# MugTempSensor2_0.net
KiCad netlist of a schematic drawn in EAGLE
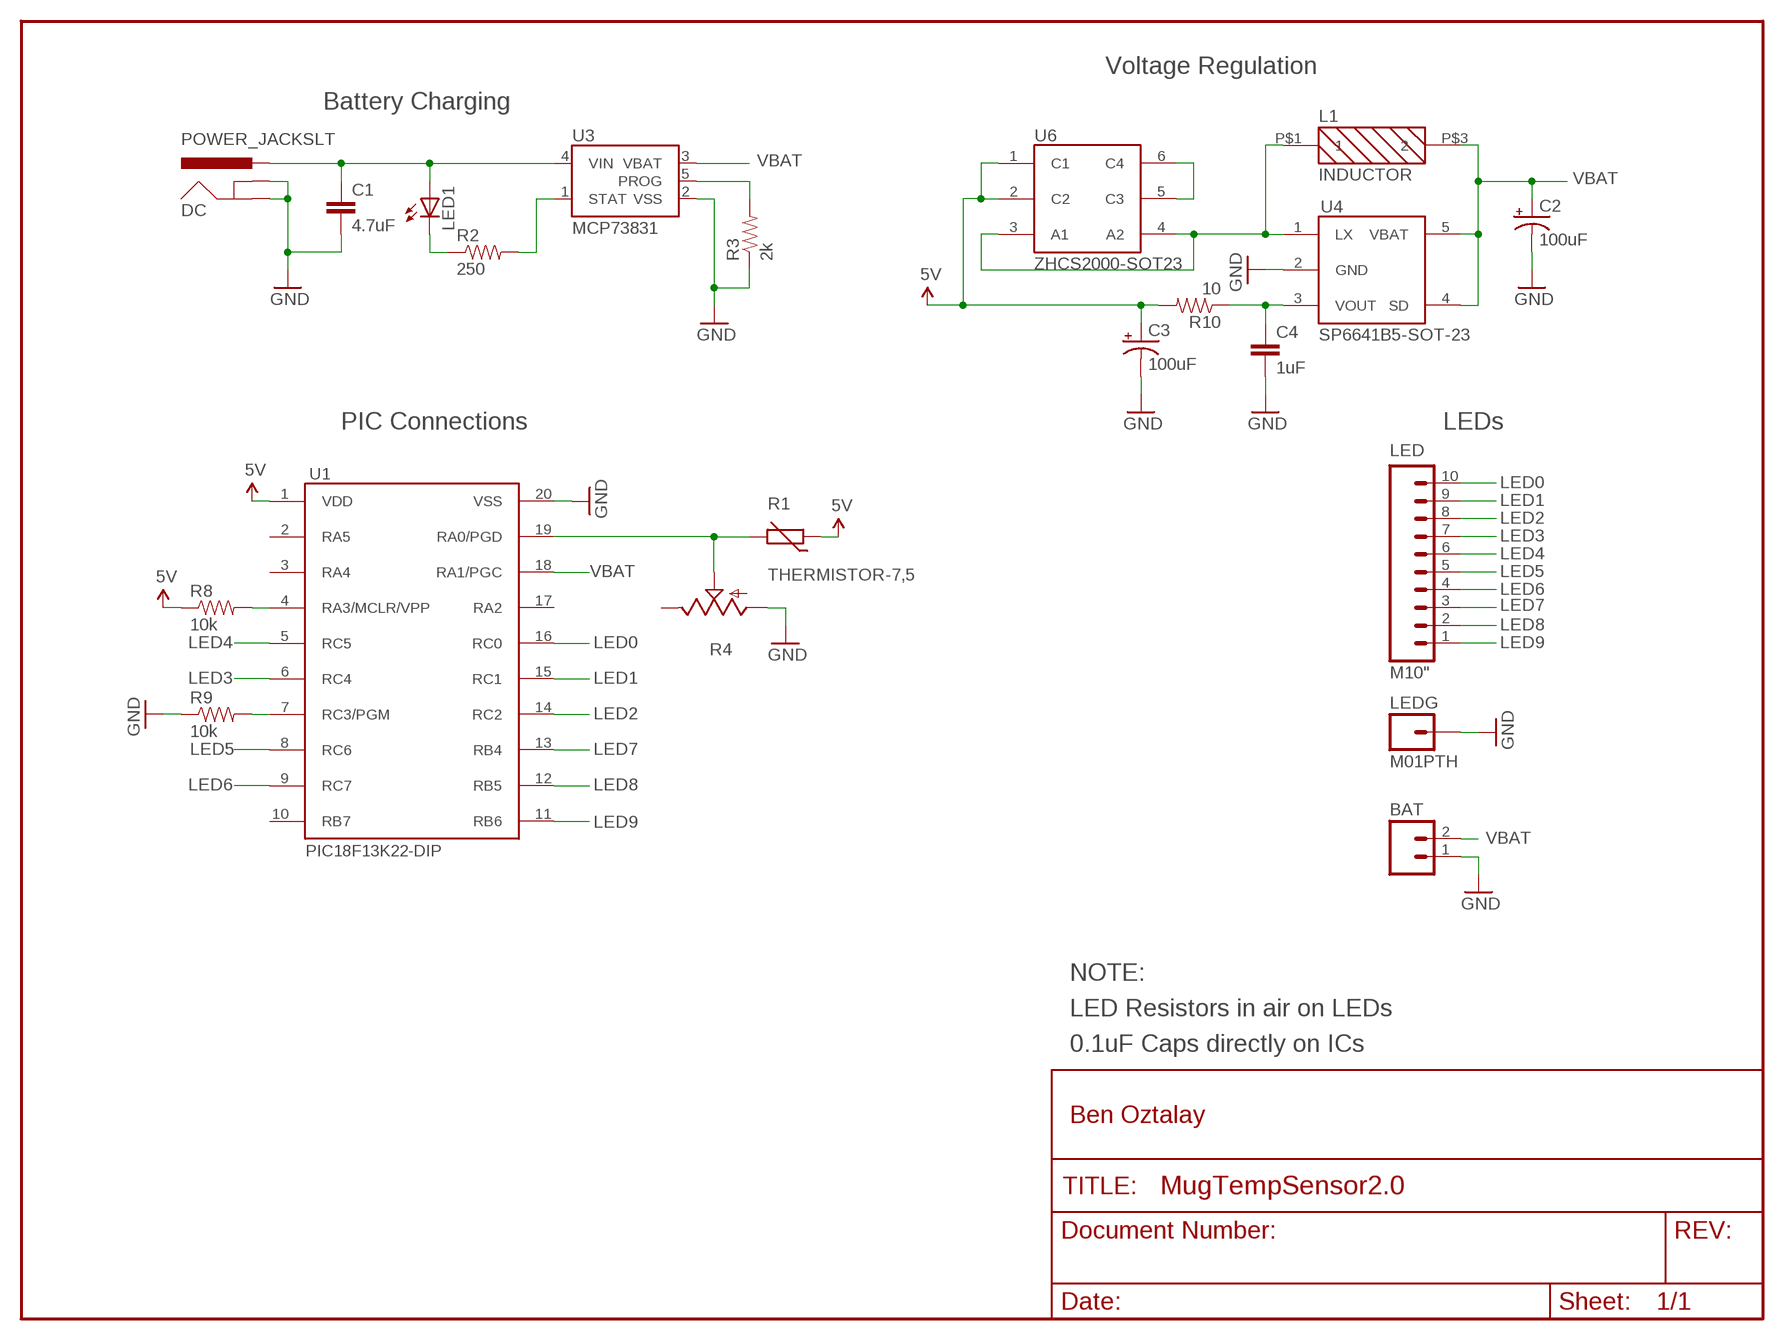
[diagram p0: schematic, sheet 1]

(export (version "E")
  (design (tool "Eeschema 10.0.6"))
  (components
    (comp (ref "BAT")
      (value "M02PTH")
      (footprint "eagle-import:1X02")
      (libsource (lib "eagle-import") (part "M02PTH"))
    )
    (comp (ref "C1")
      (value "4.7uF")
      (footprint "eagle-import:CAP-PTH-SMALL")
      (libsource (lib "eagle-import") (part "CAPPTH"))
    )
    (comp (ref "C2")
      (value "100uF")
      (footprint "eagle-import:EIA7343")
      (libsource (lib "eagle-import") (part "CAP_POL7343"))
    )
    (comp (ref "C3")
      (value "100uF")
      (footprint "eagle-import:EIA7343")
      (libsource (lib "eagle-import") (part "CAP_POL7343"))
    )
    (comp (ref "C4")
      (value "1uF")
      (footprint "eagle-import:CAP-PTH-SMALL")
      (libsource (lib "eagle-import") (part "CAPPTH"))
    )
    (comp (ref "DC")
      (value "POWER_JACKSLT")
      (footprint "eagle-import:POWER_JACK_SLOT")
      (libsource (lib "eagle-import") (part "POWER_JACKSLT"))
    )
    (comp (ref "L1")
      (value "INDUCTOR")
      (footprint "eagle-import:IND")
      (libsource (lib "eagle-import") (part "INDUCTOR"))
    )
    (comp (ref "LED")
      (value "M10\"")
      (footprint "eagle-import:1X10")
      (libsource (lib "eagle-import") (part "M10{dblquote}"))
    )
    (comp (ref "LED1")
      (value "LED3MM")
      (footprint "eagle-import:LED3MM")
      (libsource (lib "eagle-import") (part "LED3MM"))
    )
    (comp (ref "LEDG")
      (value "M01PTH")
      (footprint "eagle-import:1X01")
      (libsource (lib "eagle-import") (part "M01PTH"))
    )
    (comp (ref "R1")
      (value "THERMISTOR-7,5")
      (footprint "eagle-import:R-7,5")
      (libsource (lib "eagle-import") (part "THERMISTOR-7,5"))
    )
    (comp (ref "R2")
      (value "250")
      (footprint "eagle-import:AXIAL-0.3-KIT")
      (libsource (lib "eagle-import") (part "RESISTORKIT"))
    )
    (comp (ref "R3")
      (value "2k")
      (footprint "eagle-import:AXIAL-0.3-KIT")
      (libsource (lib "eagle-import") (part "RESISTORKIT"))
    )
    (comp (ref "R4")
      (value "TRIM_US-B64Y")
      (footprint "eagle-import:B64Y")
      (libsource (lib "eagle-import") (part "TRIM_US-B64Y"))
    )
    (comp (ref "R8")
      (value "10k")
      (footprint "eagle-import:AXIAL-0.3-KIT")
      (libsource (lib "eagle-import") (part "RESISTORKIT"))
    )
    (comp (ref "R9")
      (value "10k")
      (footprint "eagle-import:AXIAL-0.3-KIT")
      (libsource (lib "eagle-import") (part "RESISTORKIT"))
    )
    (comp (ref "R10")
      (value "10")
      (footprint "eagle-import:AXIAL-0.3-KIT")
      (libsource (lib "eagle-import") (part "RESISTORKIT"))
    )
    (comp (ref "U1")
      (value "PIC18F13K22-DIP")
      (footprint "eagle-import:DIP-20-300MIL")
      (libsource (lib "eagle-import") (part "PIC18F13K22-DIP"))
    )
    (comp (ref "U3")
      (value "MCP73831")
      (footprint "eagle-import:SOT23-5")
      (libsource (lib "eagle-import") (part "MCP73831"))
    )
    (comp (ref "U4")
      (value "SP6641B5-SOT-23")
      (footprint "eagle-import:SOT-23-5")
      (libsource (lib "eagle-import") (part "SP6641B5-SOT-23"))
    )
    (comp (ref "U6")
      (value "ZHCS2000-SOT23")
      (footprint "eagle-import:SOT-23-6")
      (libsource (lib "eagle-import") (part "ZHCS2000-SOT23"))
    )
  )
  (nets
    (net (code "1") (name "/LED0") (class "Default")
      (node (ref "LED") (pin "10") (pinfunction "10_10") (pintype "passive"))
      (node (ref "U1") (pin "16") (pinfunction "RC0_16") (pintype "bidirectional"))
    )
    (net (code "2") (name "/LED1") (class "Default")
      (node (ref "LED") (pin "9") (pinfunction "9_9") (pintype "passive"))
      (node (ref "U1") (pin "15") (pinfunction "RC1_15") (pintype "bidirectional"))
    )
    (net (code "3") (name "/LED2") (class "Default")
      (node (ref "LED") (pin "8") (pinfunction "8_8") (pintype "passive"))
      (node (ref "U1") (pin "14") (pinfunction "RC2_14") (pintype "bidirectional"))
    )
    (net (code "4") (name "/LED3") (class "Default")
      (node (ref "LED") (pin "7") (pinfunction "7_7") (pintype "passive"))
      (node (ref "U1") (pin "6") (pinfunction "RC4_6") (pintype "bidirectional"))
    )
    (net (code "5") (name "/LED4") (class "Default")
      (node (ref "LED") (pin "6") (pinfunction "6_6") (pintype "passive"))
      (node (ref "U1") (pin "5") (pinfunction "RC5_5") (pintype "bidirectional"))
    )
    (net (code "6") (name "/LED5") (class "Default")
      (node (ref "LED") (pin "5") (pinfunction "5_5") (pintype "passive"))
      (node (ref "U1") (pin "8") (pinfunction "RC6_8") (pintype "bidirectional"))
    )
    (net (code "7") (name "/LED6") (class "Default")
      (node (ref "LED") (pin "4") (pinfunction "4_4") (pintype "passive"))
      (node (ref "U1") (pin "9") (pinfunction "RC7_9") (pintype "bidirectional"))
    )
    (net (code "8") (name "/LED7") (class "Default")
      (node (ref "LED") (pin "3") (pinfunction "3_3") (pintype "passive"))
      (node (ref "U1") (pin "13") (pinfunction "RB4_13") (pintype "bidirectional"))
    )
    (net (code "9") (name "/LED8") (class "Default")
      (node (ref "LED") (pin "2") (pinfunction "2_2") (pintype "passive"))
      (node (ref "U1") (pin "12") (pinfunction "RB5_12") (pintype "bidirectional"))
    )
    (net (code "10") (name "/LED9") (class "Default")
      (node (ref "LED") (pin "1") (pinfunction "1_1") (pintype "passive"))
      (node (ref "U1") (pin "11") (pinfunction "RB6_11") (pintype "bidirectional"))
    )
    (net (code "11") (name "/VBAT") (class "Default")
      (node (ref "BAT") (pin "2") (pinfunction "2_2") (pintype "passive"))
      (node (ref "C2") (pin "A") (pinfunction "+_A") (pintype "passive"))
      (node (ref "L1") (pin "P$3") (pinfunction "2_P$3") (pintype "bidirectional"))
      (node (ref "U1") (pin "18") (pinfunction "RA1/PGC_18") (pintype "bidirectional"))
      (node (ref "U3") (pin "3") (pinfunction "VBAT_3") (pintype "power_in"))
      (node (ref "U4") (pin "4") (pinfunction "SD_4") (pintype "bidirectional"))
      (node (ref "U4") (pin "5") (pinfunction "VBAT_5") (pintype "bidirectional"))
    )
    (net (code "12") (name "5V") (class "Default")
      (node (ref "C3") (pin "A") (pinfunction "+_A") (pintype "passive"))
      (node (ref "R1") (pin "1") (pinfunction "1_1") (pintype "passive"))
      (node (ref "R10") (pin "P$2") (pinfunction "2_P$2") (pintype "passive"))
      (node (ref "R8") (pin "P$1") (pinfunction "1_P$1") (pintype "passive"))
      (node (ref "U1") (pin "1") (pinfunction "VDD_1") (pintype "bidirectional"))
      (node (ref "U6") (pin "1") (pinfunction "C1_1") (pintype "bidirectional"))
      (node (ref "U6") (pin "2") (pinfunction "C2_2") (pintype "bidirectional"))
    )
    (net (code "13") (name "GND") (class "Default")
      (node (ref "BAT") (pin "1") (pinfunction "1_1") (pintype "passive"))
      (node (ref "C1") (pin "2") (pinfunction "2_2") (pintype "passive"))
      (node (ref "C2") (pin "C") (pinfunction "-_C") (pintype "passive"))
      (node (ref "C3") (pin "C") (pinfunction "-_C") (pintype "passive"))
      (node (ref "C4") (pin "2") (pinfunction "2_2") (pintype "passive"))
      (node (ref "DC") (pin "GND@1") (pinfunction "GNDBREAK_GND@1") (pintype "bidirectional"))
      (node (ref "DC") (pin "GND@2") (pinfunction "GND_GND@2") (pintype "bidirectional"))
      (node (ref "LEDG") (pin "1") (pinfunction "1_1") (pintype "passive"))
      (node (ref "R3") (pin "P$1") (pinfunction "1_P$1") (pintype "passive"))
      (node (ref "R4") (pin "A") (pinfunction "A_A") (pintype "passive"))
      (node (ref "R9") (pin "P$1") (pinfunction "1_P$1") (pintype "passive"))
      (node (ref "U1") (pin "20") (pinfunction "VSS_20") (pintype "bidirectional"))
      (node (ref "U3") (pin "2") (pinfunction "VSS_2") (pintype "power_in"))
      (node (ref "U4") (pin "2") (pinfunction "GND_2") (pintype "bidirectional"))
    )
    (net (code "14") (name "Net-(L1-1)") (class "Default")
      (node (ref "L1") (pin "P$1") (pinfunction "1_P$1") (pintype "bidirectional"))
      (node (ref "U4") (pin "1") (pinfunction "LX_1") (pintype "bidirectional"))
      (node (ref "U6") (pin "3") (pinfunction "A1_3") (pintype "bidirectional"))
      (node (ref "U6") (pin "4") (pinfunction "A2_4") (pintype "bidirectional"))
    )
    (net (code "15") (name "Net-(LED1-C)") (class "Default")
      (node (ref "LED1") (pin "K") (pinfunction "C_K") (pintype "passive"))
      (node (ref "R2") (pin "P$1") (pinfunction "1_P$1") (pintype "passive"))
    )
    (net (code "16") (name "Net-(R2-2)") (class "Default")
      (node (ref "R2") (pin "P$2") (pinfunction "2_P$2") (pintype "passive"))
      (node (ref "U3") (pin "1") (pinfunction "STAT_1") (pintype "output"))
    )
    (net (code "17") (name "Net-(R3-2)") (class "Default")
      (node (ref "R3") (pin "P$2") (pinfunction "2_P$2") (pintype "passive"))
      (node (ref "U3") (pin "5") (pinfunction "PROG_5") (pintype "input"))
    )
    (net (code "18") (name "Net-(R8-2)") (class "Default")
      (node (ref "R8") (pin "P$2") (pinfunction "2_P$2") (pintype "passive"))
      (node (ref "U1") (pin "4") (pinfunction "RA3/MCLR/VPP_4") (pintype "bidirectional"))
    )
    (net (code "19") (name "Net-(R9-2)") (class "Default")
      (node (ref "R9") (pin "P$2") (pinfunction "2_P$2") (pintype "passive"))
      (node (ref "U1") (pin "7") (pinfunction "RC3/PGM_7") (pintype "bidirectional"))
    )
    (net (code "20") (name "Net-(R10-1)") (class "Default")
      (node (ref "C4") (pin "1") (pinfunction "1_1") (pintype "passive"))
      (node (ref "R10") (pin "P$1") (pinfunction "1_P$1") (pintype "passive"))
      (node (ref "U4") (pin "3") (pinfunction "VOUT_3") (pintype "bidirectional"))
    )
    (net (code "21") (name "Net-(U1-RA0{slash}PGD)") (class "Default")
      (node (ref "R1") (pin "2") (pinfunction "2_2") (pintype "passive"))
      (node (ref "R4") (pin "S") (pinfunction "S_S") (pintype "passive"))
      (node (ref "U1") (pin "19") (pinfunction "RA0/PGD_19") (pintype "bidirectional"))
    )
    (net (code "22") (name "Net-(U3-VIN)") (class "Default")
      (node (ref "C1") (pin "1") (pinfunction "1_1") (pintype "passive"))
      (node (ref "DC") (pin "PWR") (pinfunction "PWR_PWR") (pintype "bidirectional"))
      (node (ref "LED1") (pin "A") (pinfunction "A_A") (pintype "passive"))
      (node (ref "U3") (pin "4") (pinfunction "VIN_4") (pintype "power_in"))
    )
    (net (code "23") (name "Net-(U6-C3)") (class "Default")
      (node (ref "U6") (pin "5") (pinfunction "C3_5") (pintype "bidirectional"))
      (node (ref "U6") (pin "6") (pinfunction "C4_6") (pintype "bidirectional"))
    )
    (net (code "24") (name "unconnected-(R4-PadE)") (class "Default")
      (node (ref "R4") (pin "E") (pinfunction "E_E") (pintype "passive"))
    )
    (net (code "25") (name "unconnected-(U1-RA2-Pad17)") (class "Default")
      (node (ref "U1") (pin "17") (pinfunction "RA2_17") (pintype "bidirectional"))
    )
    (net (code "26") (name "unconnected-(U1-RA4-Pad3)") (class "Default")
      (node (ref "U1") (pin "3") (pinfunction "RA4_3") (pintype "bidirectional"))
    )
    (net (code "27") (name "unconnected-(U1-RA5-Pad2)") (class "Default")
      (node (ref "U1") (pin "2") (pinfunction "RA5_2") (pintype "bidirectional"))
    )
    (net (code "28") (name "unconnected-(U1-RB7-Pad10)") (class "Default")
      (node (ref "U1") (pin "10") (pinfunction "RB7_10") (pintype "bidirectional"))
    )
  )
)
